# offzone-addon-s7-easyeda.net
KiCad netlist of a schematic drawn in EasyEDA
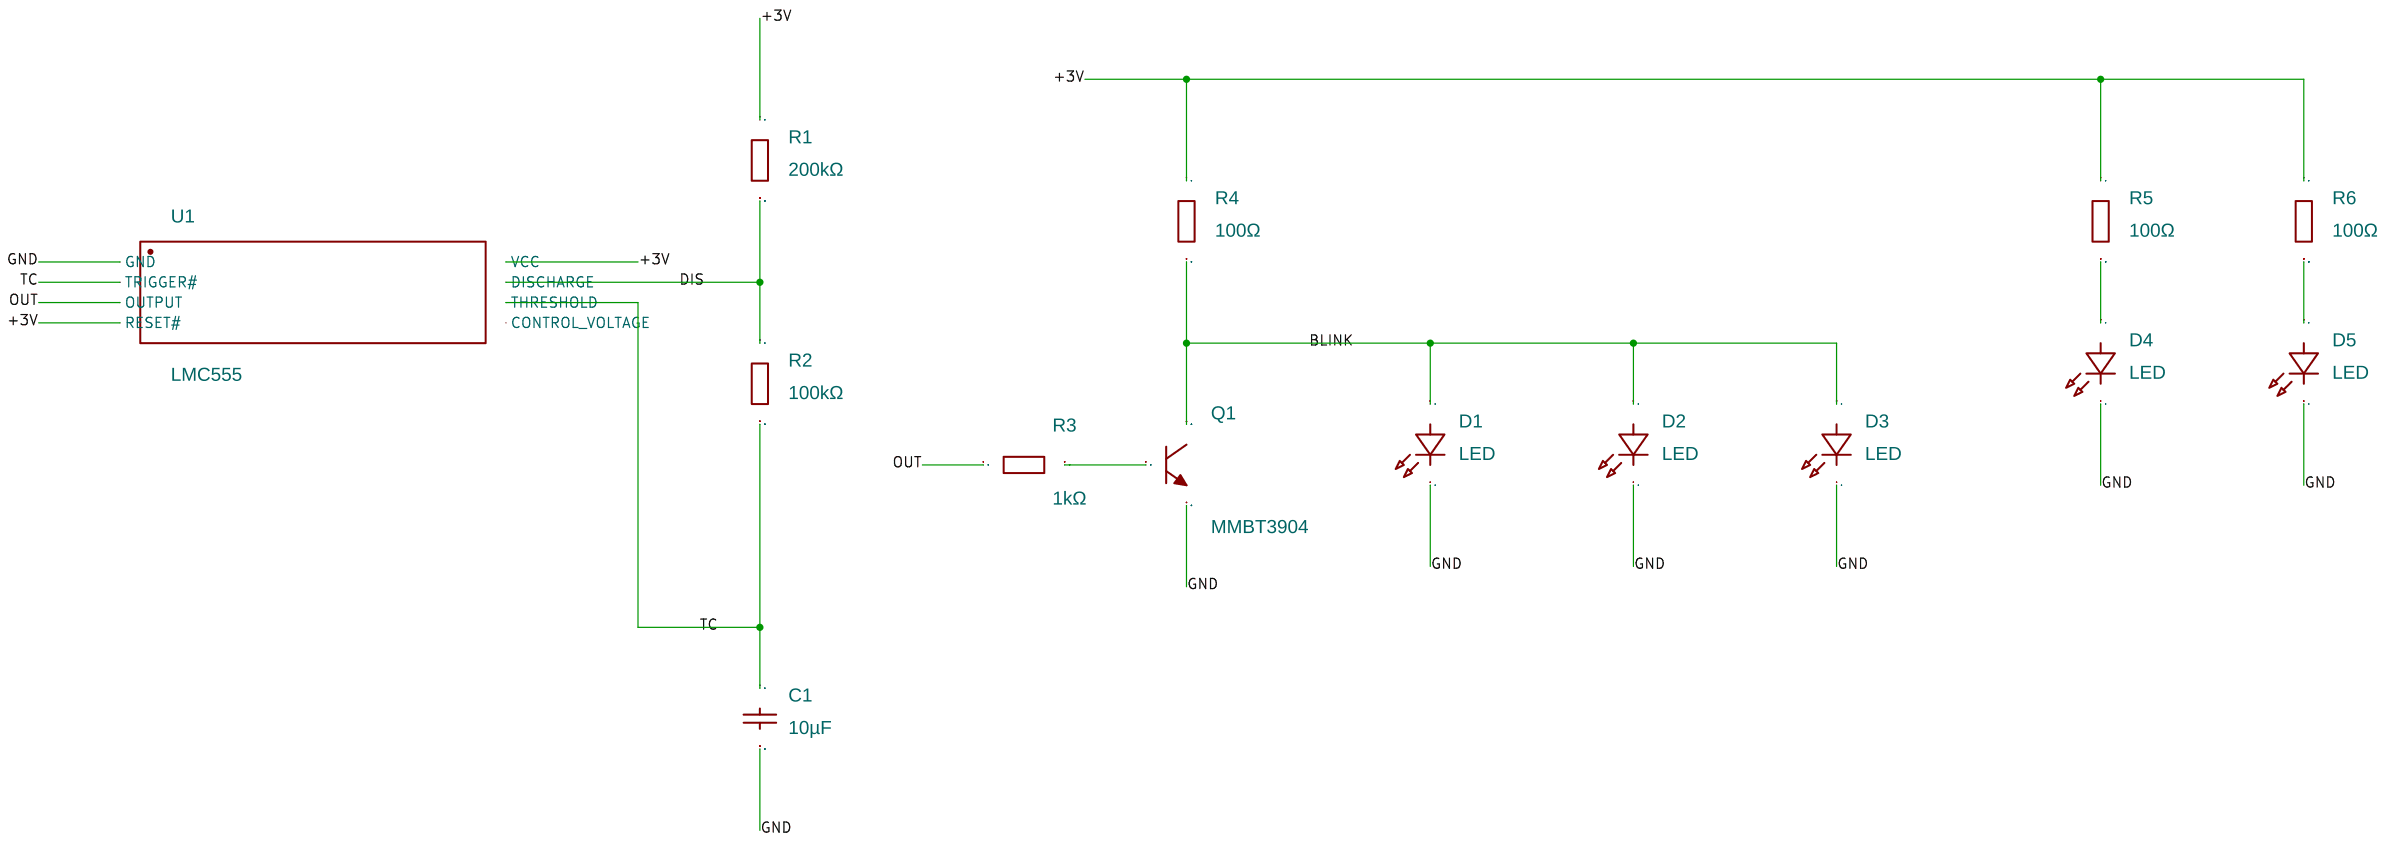
[diagram p0: schematic sheet]

(export (version "E")
  (design (tool "Eeschema 10.0.6"))
  (components
    (comp (ref "C1")
      (value "10µF")
      (fields
        (field (name "BOM_Manufacturer Part") "CL21A106KOQNNNE")
        (field (name "BOM_Supplier Part") "C1713")
      )
      (libsource (lib "") (part "CL21A106KOQNNNE"))
    )
    (comp (ref "D1")
      (value "LED")
      (fields
        (field (name "BOM_Manufacturer Part") "17-21/R6C-AQ2R2B/4T")
        (field (name "BOM_Supplier Part") "C2971979")
      )
      (libsource (lib "") (part "17-21/R6C-AQ2R2B/4T"))
    )
    (comp (ref "D2")
      (value "LED")
      (fields
        (field (name "BOM_Manufacturer Part") "17-21/R6C-AQ2R2B/4T")
        (field (name "BOM_Supplier Part") "C2971979")
      )
      (libsource (lib "") (part "17-21/R6C-AQ2R2B/4T"))
    )
    (comp (ref "D3")
      (value "LED")
      (fields
        (field (name "BOM_Manufacturer Part") "17-21/R6C-AQ2R2B/4T")
        (field (name "BOM_Supplier Part") "C2971979")
      )
      (libsource (lib "") (part "17-21/R6C-AQ2R2B/4T"))
    )
    (comp (ref "D4")
      (value "LED")
      (fields
        (field (name "BOM_Manufacturer Part") "17-21/R6C-AQ2R2B/4T")
        (field (name "BOM_Supplier Part") "C2971979")
      )
      (libsource (lib "") (part "17-21/R6C-AQ2R2B/4T"))
    )
    (comp (ref "D5")
      (value "LED")
      (fields
        (field (name "BOM_Manufacturer Part") "17-21/R6C-AQ2R2B/4T")
        (field (name "BOM_Supplier Part") "C2971979")
      )
      (libsource (lib "") (part "17-21/R6C-AQ2R2B/4T"))
    )
    (comp (ref "Q1")
      (value "MMBT3904")
      (fields
        (field (name "BOM_Manufacturer Part") "MMBT3904LT1G")
        (field (name "BOM_Supplier Part") "C81464")
      )
      (libsource (lib "") (part "MMBT3904LT1G"))
    )
    (comp (ref "R1")
      (value "200kΩ")
      (fields
        (field (name "BOM_Manufacturer Part") "0603WAF2003T5E")
        (field (name "BOM_Supplier Part") "C25811")
      )
      (libsource (lib "") (part "0603WAF2003T5E"))
    )
    (comp (ref "R2")
      (value "100kΩ")
      (fields
        (field (name "BOM_Manufacturer Part") "0603WAF1003T5E")
        (field (name "BOM_Supplier Part") "C25803")
      )
      (libsource (lib "") (part "0603WAF1003T5E"))
    )
    (comp (ref "R3")
      (value "1kΩ")
      (fields
        (field (name "BOM_Manufacturer Part") "0603WAF1001T5E")
        (field (name "BOM_Supplier Part") "C21190")
      )
      (libsource (lib "") (part "0603WAF1001T5E"))
    )
    (comp (ref "R4")
      (value "100Ω")
      (fields
        (field (name "BOM_Manufacturer Part") "RC0603FR-07100RL")
        (field (name "BOM_Supplier Part") "C105588")
      )
      (libsource (lib "") (part "RC0603FR-07100RL"))
    )
    (comp (ref "R5")
      (value "100Ω")
      (fields
        (field (name "BOM_Manufacturer Part") "RC0603FR-07100RL")
        (field (name "BOM_Supplier Part") "C105588")
      )
      (libsource (lib "") (part "RC0603FR-07100RL"))
    )
    (comp (ref "R6")
      (value "100Ω")
      (fields
        (field (name "BOM_Manufacturer Part") "RC0603FR-07100RL")
        (field (name "BOM_Supplier Part") "C105588")
      )
      (libsource (lib "") (part "RC0603FR-07100RL"))
    )
    (comp (ref "U1")
      (value "LMC555")
      (fields
        (field (name "BOM_Manufacturer Part") "LMC555M/TR")
        (field (name "BOM_Supplier Part") "C356725")
      )
      (libsource (lib "") (part "LMC555M/TR"))
    )
  )
  (nets
    (net (code "1") (name "/+3V") (class "Default")
      (node (ref "R1") (pin "1") (pinfunction "1_1") (pintype "input"))
      (node (ref "R4") (pin "1") (pinfunction "1_1") (pintype "input"))
      (node (ref "R5") (pin "1") (pinfunction "1_1") (pintype "input"))
      (node (ref "R6") (pin "1") (pinfunction "1_1") (pintype "input"))
      (node (ref "U1") (pin "4") (pinfunction "RESET#_4") (pintype "unspecified"))
      (node (ref "U1") (pin "8") (pinfunction "VCC_8") (pintype "unspecified"))
    )
    (net (code "2") (name "/BLINK") (class "Default")
      (node (ref "D1") (pin "2") (pinfunction "A_2") (pintype "unspecified"))
      (node (ref "D2") (pin "2") (pinfunction "A_2") (pintype "unspecified"))
      (node (ref "D3") (pin "2") (pinfunction "A_2") (pintype "unspecified"))
      (node (ref "Q1") (pin "3") (pinfunction "3_3") (pintype "input"))
      (node (ref "R4") (pin "2") (pinfunction "2_2") (pintype "input"))
    )
    (net (code "3") (name "/DIS") (class "Default")
      (node (ref "R1") (pin "2") (pinfunction "2_2") (pintype "input"))
      (node (ref "R2") (pin "1") (pinfunction "1_1") (pintype "input"))
      (node (ref "U1") (pin "7") (pinfunction "DISCHARGE_7") (pintype "unspecified"))
    )
    (net (code "4") (name "/GND") (class "Default")
      (node (ref "C1") (pin "2") (pinfunction "2_2") (pintype "input"))
      (node (ref "D1") (pin "1") (pinfunction "K_1") (pintype "unspecified"))
      (node (ref "D2") (pin "1") (pinfunction "K_1") (pintype "unspecified"))
      (node (ref "D3") (pin "1") (pinfunction "K_1") (pintype "unspecified"))
      (node (ref "D4") (pin "1") (pinfunction "K_1") (pintype "unspecified"))
      (node (ref "D5") (pin "1") (pinfunction "K_1") (pintype "unspecified"))
      (node (ref "Q1") (pin "2") (pinfunction "2_2") (pintype "input"))
      (node (ref "U1") (pin "1") (pinfunction "GND_1") (pintype "unspecified"))
    )
    (net (code "5") (name "/OUT") (class "Default")
      (node (ref "R3") (pin "1") (pinfunction "1_1") (pintype "input"))
      (node (ref "U1") (pin "3") (pinfunction "OUTPUT_3") (pintype "unspecified"))
    )
    (net (code "6") (name "/TC") (class "Default")
      (node (ref "C1") (pin "1") (pinfunction "1_1") (pintype "input"))
      (node (ref "R2") (pin "2") (pinfunction "2_2") (pintype "input"))
      (node (ref "U1") (pin "2") (pinfunction "TRIGGER#_2") (pintype "unspecified"))
      (node (ref "U1") (pin "6") (pinfunction "THRESHOLD_6") (pintype "unspecified"))
    )
    (net (code "7") (name "Net-(D4-A)") (class "Default")
      (node (ref "D4") (pin "2") (pinfunction "A_2") (pintype "unspecified"))
      (node (ref "R5") (pin "2") (pinfunction "2_2") (pintype "input"))
    )
    (net (code "8") (name "Net-(D5-A)") (class "Default")
      (node (ref "D5") (pin "2") (pinfunction "A_2") (pintype "unspecified"))
      (node (ref "R6") (pin "2") (pinfunction "2_2") (pintype "input"))
    )
    (net (code "9") (name "Net-(Q1-Pad1)") (class "Default")
      (node (ref "Q1") (pin "1") (pinfunction "1_1") (pintype "input"))
      (node (ref "R3") (pin "2") (pinfunction "2_2") (pintype "input"))
    )
    (net (code "10") (name "unconnected-(U1-CONTROL_VOLTAGE-Pad5)") (class "Default")
      (node (ref "U1") (pin "5") (pinfunction "CONTROL_VOLTAGE_5") (pintype "unspecified"))
    )
  )
)
